# tba810as_stereo.net
KiCad netlist of a schematic drawn in EAGLE
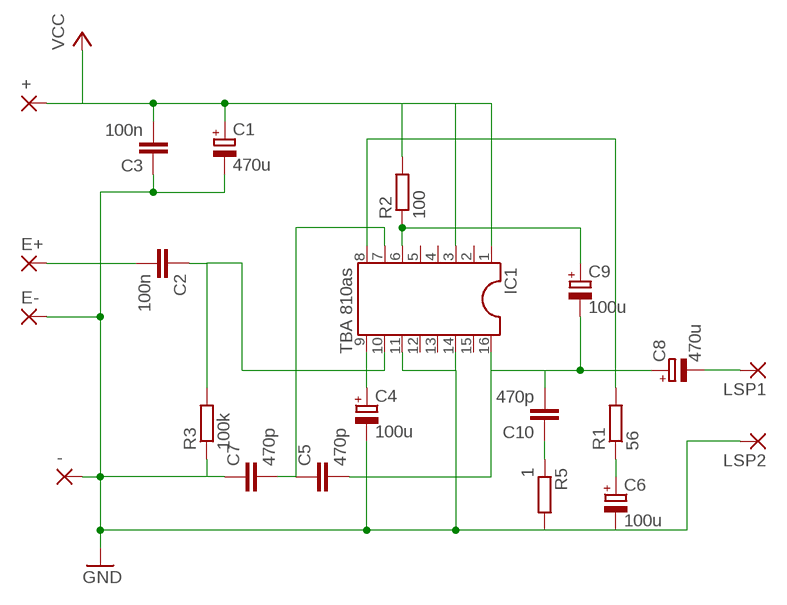
[diagram p0: schematic, sheet 1]

(export (version "E")
  (design (tool "Eeschema 10.0.6"))
  (components
    (comp (ref "+")
      (value "2,15/1,0")
      (footprint "eagle-import:2,15_1,0")
      (libsource (lib "eagle-import") (part "2,15/1,0"))
    )
    (comp (ref "-")
      (value "2,15/1,0")
      (footprint "eagle-import:2,15_1,0")
      (libsource (lib "eagle-import") (part "2,15/1,0"))
    )
    (comp (ref "C1")
      (value "470u")
      (footprint "eagle-import:E5-8,5")
      (libsource (lib "eagle-import") (part "CPOL-EUE5-8.5"))
    )
    (comp (ref "C2")
      (value "100n")
      (footprint "eagle-import:C025-024X044")
      (libsource (lib "eagle-import") (part "C-EU025-024X044"))
    )
    (comp (ref "C3")
      (value "100n")
      (footprint "eagle-import:C025-024X044")
      (libsource (lib "eagle-import") (part "C-EU025-024X044"))
    )
    (comp (ref "C4")
      (value "100u")
      (footprint "eagle-import:E2,5-5")
      (libsource (lib "eagle-import") (part "CPOL-EUE2.5-5"))
    )
    (comp (ref "C5")
      (value "470p")
      (footprint "eagle-import:C025-024X044")
      (libsource (lib "eagle-import") (part "C-EU025-024X044"))
    )
    (comp (ref "C6")
      (value "100u")
      (footprint "eagle-import:E2,5-5")
      (libsource (lib "eagle-import") (part "CPOL-EUE2.5-5"))
    )
    (comp (ref "C7")
      (value "470p")
      (footprint "eagle-import:C025-024X044")
      (libsource (lib "eagle-import") (part "C-EU025-024X044"))
    )
    (comp (ref "C8")
      (value "470u")
      (footprint "eagle-import:E5-8,5")
      (libsource (lib "eagle-import") (part "CPOL-EUE5-8.5"))
    )
    (comp (ref "C9")
      (value "100u")
      (footprint "eagle-import:E2,5-5")
      (libsource (lib "eagle-import") (part "CPOL-EUE2.5-5"))
    )
    (comp (ref "C10")
      (value "470p")
      (footprint "eagle-import:C025-024X044")
      (libsource (lib "eagle-import") (part "C-EU025-024X044"))
    )
    (comp (ref "E+")
      (value "2,15/1,0")
      (footprint "eagle-import:2,15_1,0")
      (libsource (lib "eagle-import") (part "2,15/1,0"))
    )
    (comp (ref "E-")
      (value "2,15/1,0")
      (footprint "eagle-import:2,15_1,0")
      (libsource (lib "eagle-import") (part "2,15/1,0"))
    )
    (comp (ref "IC1")
      (value "TBA 810as")
      (footprint "eagle-import:DIL16")
      (libsource (lib "eagle-import") (part "DIL16"))
    )
    (comp (ref "LSP1")
      (value "2,15/1,0")
      (footprint "eagle-import:2,15_1,0")
      (libsource (lib "eagle-import") (part "2,15/1,0"))
    )
    (comp (ref "LSP2")
      (value "2,15/1,0")
      (footprint "eagle-import:2,15_1,0")
      (libsource (lib "eagle-import") (part "2,15/1,0"))
    )
    (comp (ref "R1")
      (value "56")
      (footprint "eagle-import:0207_7")
      (libsource (lib "eagle-import") (part "R-EU_0207/7"))
    )
    (comp (ref "R2")
      (value "100")
      (footprint "eagle-import:0207_7")
      (libsource (lib "eagle-import") (part "R-EU_0207/7"))
    )
    (comp (ref "R3")
      (value "100k")
      (footprint "eagle-import:0207_7")
      (libsource (lib "eagle-import") (part "R-EU_0207/7"))
    )
    (comp (ref "R5")
      (value "1")
      (footprint "eagle-import:0207_7")
      (libsource (lib "eagle-import") (part "R-EU_0207/7"))
    )
  )
  (nets
    (net (code "1") (name "GND") (class "Default")
      (node (ref "-") (pin "1") (pinfunction "P_1") (pintype "passive"))
      (node (ref "C1") (pin "-") (pinfunction "-_-") (pintype "passive"))
      (node (ref "C3") (pin "1") (pinfunction "1_1") (pintype "passive"))
      (node (ref "C4") (pin "-") (pinfunction "-_-") (pintype "passive"))
      (node (ref "C6") (pin "-") (pinfunction "-_-") (pintype "passive"))
      (node (ref "C7") (pin "1") (pinfunction "1_1") (pintype "passive"))
      (node (ref "E-") (pin "1") (pinfunction "P_1") (pintype "passive"))
      (node (ref "IC1") (pin "11") (pinfunction "11_11") (pintype "passive"))
      (node (ref "IC1") (pin "14") (pinfunction "14_14") (pintype "passive"))
      (node (ref "LSP2") (pin "1") (pinfunction "P_1") (pintype "passive"))
      (node (ref "R3") (pin "1") (pinfunction "1_1") (pintype "passive"))
      (node (ref "R5") (pin "2") (pinfunction "2_2") (pintype "passive"))
    )
    (net (code "2") (name "Net-(C2-Pad1)") (class "Default")
      (node (ref "C2") (pin "1") (pinfunction "1_1") (pintype "passive"))
      (node (ref "IC1") (pin "10") (pinfunction "10_10") (pintype "passive"))
      (node (ref "R3") (pin "2") (pinfunction "2_2") (pintype "passive"))
    )
    (net (code "3") (name "Net-(C4-Pad+)") (class "Default")
      (node (ref "C4") (pin "+") (pinfunction "+_+") (pintype "passive"))
      (node (ref "IC1") (pin "9") (pinfunction "9_9") (pintype "passive"))
    )
    (net (code "4") (name "Net-(C5-Pad1)") (class "Default")
      (node (ref "C5") (pin "1") (pinfunction "1_1") (pintype "passive"))
      (node (ref "C7") (pin "2") (pinfunction "2_2") (pintype "passive"))
      (node (ref "IC1") (pin "7") (pinfunction "7_7") (pintype "passive"))
    )
    (net (code "5") (name "Net-(C6-Pad+)") (class "Default")
      (node (ref "C6") (pin "+") (pinfunction "+_+") (pintype "passive"))
      (node (ref "R1") (pin "1") (pinfunction "1_1") (pintype "passive"))
    )
    (net (code "6") (name "Net-(C9-Pad+)") (class "Default")
      (node (ref "C9") (pin "+") (pinfunction "+_+") (pintype "passive"))
      (node (ref "IC1") (pin "6") (pinfunction "6_6") (pintype "passive"))
      (node (ref "R2") (pin "1") (pinfunction "1_1") (pintype "passive"))
    )
    (net (code "7") (name "Net-(C10-Pad1)") (class "Default")
      (node (ref "C10") (pin "1") (pinfunction "1_1") (pintype "passive"))
      (node (ref "R5") (pin "1") (pinfunction "1_1") (pintype "passive"))
    )
    (net (code "8") (name "Net-(C10-Pad2)") (class "Default")
      (node (ref "C10") (pin "2") (pinfunction "2_2") (pintype "passive"))
      (node (ref "C5") (pin "2") (pinfunction "2_2") (pintype "passive"))
      (node (ref "C8") (pin "+") (pinfunction "+_+") (pintype "passive"))
      (node (ref "C9") (pin "-") (pinfunction "-_-") (pintype "passive"))
      (node (ref "IC1") (pin "16") (pinfunction "16_16") (pintype "passive"))
    )
    (net (code "9") (name "Net-(E+-P)") (class "Default")
      (node (ref "C2") (pin "2") (pinfunction "2_2") (pintype "passive"))
      (node (ref "E+") (pin "1") (pinfunction "P_1") (pintype "passive"))
    )
    (net (code "10") (name "Net-(IC1-Pad8)") (class "Default")
      (node (ref "IC1") (pin "8") (pinfunction "8_8") (pintype "passive"))
      (node (ref "R1") (pin "2") (pinfunction "2_2") (pintype "passive"))
    )
    (net (code "11") (name "Net-(LSP1-P)") (class "Default")
      (node (ref "C8") (pin "-") (pinfunction "-_-") (pintype "passive"))
      (node (ref "LSP1") (pin "1") (pinfunction "P_1") (pintype "passive"))
    )
    (net (code "12") (name "VCC") (class "Default")
      (node (ref "+") (pin "1") (pinfunction "P_1") (pintype "passive"))
      (node (ref "C1") (pin "+") (pinfunction "+_+") (pintype "passive"))
      (node (ref "C3") (pin "2") (pinfunction "2_2") (pintype "passive"))
      (node (ref "IC1") (pin "1") (pinfunction "1_1") (pintype "passive"))
      (node (ref "IC1") (pin "3") (pinfunction "3_3") (pintype "passive"))
      (node (ref "R2") (pin "2") (pinfunction "2_2") (pintype "passive"))
    )
    (net (code "13") (name "unconnected-(IC1-Pad2)") (class "Default")
      (node (ref "IC1") (pin "2") (pinfunction "2_2") (pintype "passive"))
    )
    (net (code "14") (name "unconnected-(IC1-Pad4)") (class "Default")
      (node (ref "IC1") (pin "4") (pinfunction "4_4") (pintype "passive"))
    )
    (net (code "15") (name "unconnected-(IC1-Pad5)") (class "Default")
      (node (ref "IC1") (pin "5") (pinfunction "5_5") (pintype "passive"))
    )
    (net (code "16") (name "unconnected-(IC1-Pad12)") (class "Default")
      (node (ref "IC1") (pin "12") (pinfunction "12_12") (pintype "passive"))
    )
    (net (code "17") (name "unconnected-(IC1-Pad13)") (class "Default")
      (node (ref "IC1") (pin "13") (pinfunction "13_13") (pintype "passive"))
    )
    (net (code "18") (name "unconnected-(IC1-Pad15)") (class "Default")
      (node (ref "IC1") (pin "15") (pinfunction "15_15") (pintype "passive"))
    )
  )
)
